# input_device_2.net
KiCad netlist of a schematic drawn in EAGLE
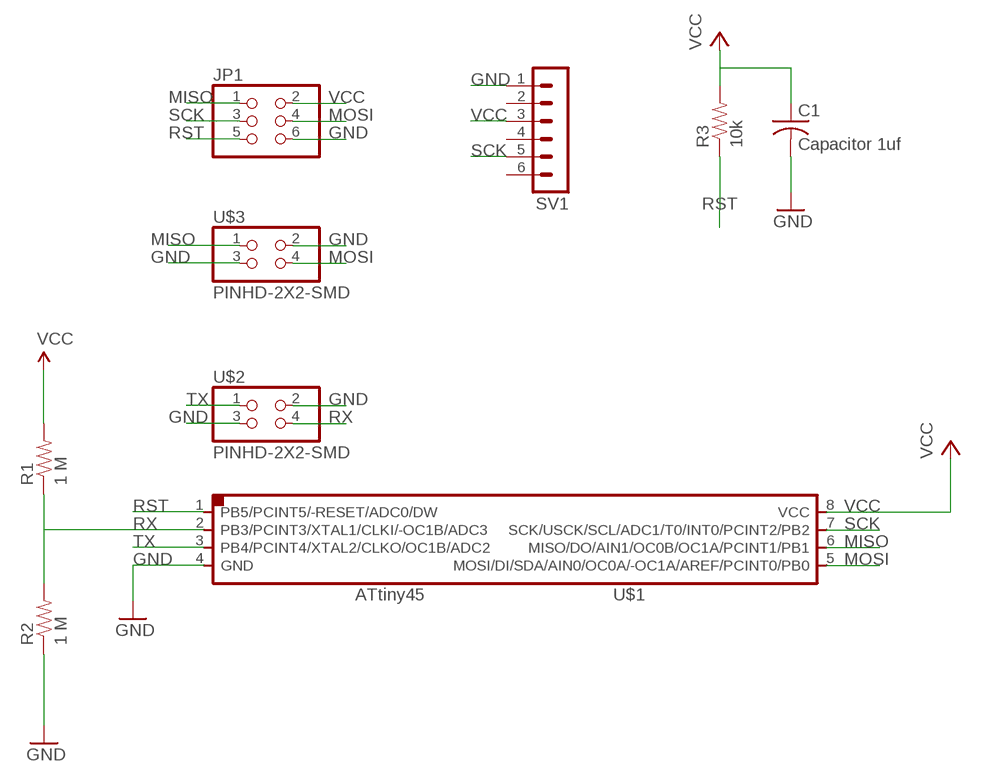
[diagram p0: schematic, sheet 1]

(export (version "E")
  (design (tool "Eeschema 10.0.6"))
  (components
    (comp (ref "C1")
      (value "Capacitor 1uf")
      (footprint "eagle-import:C1206")
      (libsource (lib "eagle-import") (part "C-USC1206"))
    )
    (comp (ref "JP1")
      (value "PINHD-2X3-SMD")
      (footprint "eagle-import:2X03SMD")
      (libsource (lib "eagle-import") (part "PINHD-2X3-SMD"))
    )
    (comp (ref "R1")
      (value "1 M")
      (footprint "eagle-import:1206")
      (libsource (lib "eagle-import") (part "RESISTOR1206"))
    )
    (comp (ref "R2")
      (value "1 M")
      (footprint "eagle-import:1206")
      (libsource (lib "eagle-import") (part "RESISTOR1206"))
    )
    (comp (ref "R3")
      (value "10k")
      (footprint "eagle-import:1206")
      (libsource (lib "eagle-import") (part "RESISTOR1206"))
    )
    (comp (ref "SV1")
      (value "MA06-1")
      (footprint "eagle-import:MA06-1")
      (libsource (lib "eagle-import") (part "MA06-1"))
    )
    (comp (ref "U$1")
      (value "ATTINY45SI")
      (footprint "eagle-import:SOIC8")
      (libsource (lib "eagle-import") (part "ATTINY45SI"))
    )
    (comp (ref "U$2")
      (value "PINHD-2X2-SMD")
      (footprint "eagle-import:2X02SMD")
      (libsource (lib "eagle-import") (part "PINHD-2X2-SMD"))
    )
    (comp (ref "U$3")
      (value "PINHD-2X2-SMD")
      (footprint "eagle-import:2X02SMD")
      (libsource (lib "eagle-import") (part "PINHD-2X2-SMD"))
    )
  )
  (nets
    (net (code "1") (name "/MISO") (class "Default")
      (node (ref "JP1") (pin "1") (pinfunction "1_1") (pintype "passive"))
      (node (ref "U$1") (pin "6") (pinfunction "MISO/DO/AIN1/OC0B/OC1A/PCINT1/PB1_6") (pintype "bidirectional"))
      (node (ref "U$3") (pin "1") (pinfunction "1_1") (pintype "passive"))
    )
    (net (code "2") (name "/MOSI") (class "Default")
      (node (ref "JP1") (pin "4") (pinfunction "4_4") (pintype "passive"))
      (node (ref "U$1") (pin "5") (pinfunction "MOSI/DI/SDA/AIN0/OC0A/-OC1A/AREF/PCINT0/PB0_5") (pintype "bidirectional"))
      (node (ref "U$3") (pin "4") (pinfunction "4_4") (pintype "passive"))
    )
    (net (code "3") (name "/RST") (class "Default")
      (node (ref "JP1") (pin "5") (pinfunction "5_5") (pintype "passive"))
      (node (ref "R3") (pin "1") (pinfunction "1_1") (pintype "passive"))
      (node (ref "U$1") (pin "1") (pinfunction "PB5/PCINT5/-RESET/ADC0/DW_1") (pintype "bidirectional"))
    )
    (net (code "4") (name "/RX") (class "Default")
      (node (ref "R1") (pin "1") (pinfunction "1_1") (pintype "passive"))
      (node (ref "R2") (pin "2") (pinfunction "2_2") (pintype "passive"))
      (node (ref "U$1") (pin "2") (pinfunction "PB3/PCINT3/XTAL1/CLKI/-OC1B/ADC3_2") (pintype "bidirectional"))
      (node (ref "U$2") (pin "4") (pinfunction "4_4") (pintype "passive"))
    )
    (net (code "5") (name "/SCK") (class "Default")
      (node (ref "JP1") (pin "3") (pinfunction "3_3") (pintype "passive"))
      (node (ref "SV1") (pin "5") (pinfunction "5_5") (pintype "passive"))
      (node (ref "U$1") (pin "7") (pinfunction "SCK/USCK/SCL/ADC1/T0/INT0/PCINT2/PB2_7") (pintype "bidirectional"))
    )
    (net (code "6") (name "/TX") (class "Default")
      (node (ref "U$1") (pin "3") (pinfunction "PB4/PCINT4/XTAL2/CLKO/OC1B/ADC2_3") (pintype "bidirectional"))
      (node (ref "U$2") (pin "1") (pinfunction "1_1") (pintype "passive"))
    )
    (net (code "7") (name "GND") (class "Default")
      (node (ref "C1") (pin "2") (pinfunction "2_2") (pintype "passive"))
      (node (ref "JP1") (pin "6") (pinfunction "6_6") (pintype "passive"))
      (node (ref "R2") (pin "1") (pinfunction "1_1") (pintype "passive"))
      (node (ref "SV1") (pin "1") (pinfunction "1_1") (pintype "passive"))
      (node (ref "U$1") (pin "4") (pinfunction "GND_4") (pintype "bidirectional"))
      (node (ref "U$2") (pin "2") (pinfunction "2_2") (pintype "passive"))
      (node (ref "U$2") (pin "3") (pinfunction "3_3") (pintype "passive"))
      (node (ref "U$3") (pin "2") (pinfunction "2_2") (pintype "passive"))
      (node (ref "U$3") (pin "3") (pinfunction "3_3") (pintype "passive"))
    )
    (net (code "8") (name "VCC") (class "Default")
      (node (ref "C1") (pin "1") (pinfunction "1_1") (pintype "passive"))
      (node (ref "JP1") (pin "2") (pinfunction "2_2") (pintype "passive"))
      (node (ref "R1") (pin "2") (pinfunction "2_2") (pintype "passive"))
      (node (ref "R3") (pin "2") (pinfunction "2_2") (pintype "passive"))
      (node (ref "SV1") (pin "3") (pinfunction "3_3") (pintype "passive"))
      (node (ref "U$1") (pin "8") (pinfunction "VCC_8") (pintype "bidirectional"))
    )
    (net (code "9") (name "unconnected-(SV1-Pad2)") (class "Default")
      (node (ref "SV1") (pin "2") (pinfunction "2_2") (pintype "passive"))
    )
    (net (code "10") (name "unconnected-(SV1-Pad4)") (class "Default")
      (node (ref "SV1") (pin "4") (pinfunction "4_4") (pintype "passive"))
    )
    (net (code "11") (name "unconnected-(SV1-Pad6)") (class "Default")
      (node (ref "SV1") (pin "6") (pinfunction "6_6") (pintype "passive"))
    )
  )
)
